# EasyEda_SCH_tally_light_-_main_board_202.net
KiCad netlist of a schematic drawn in EasyEDA
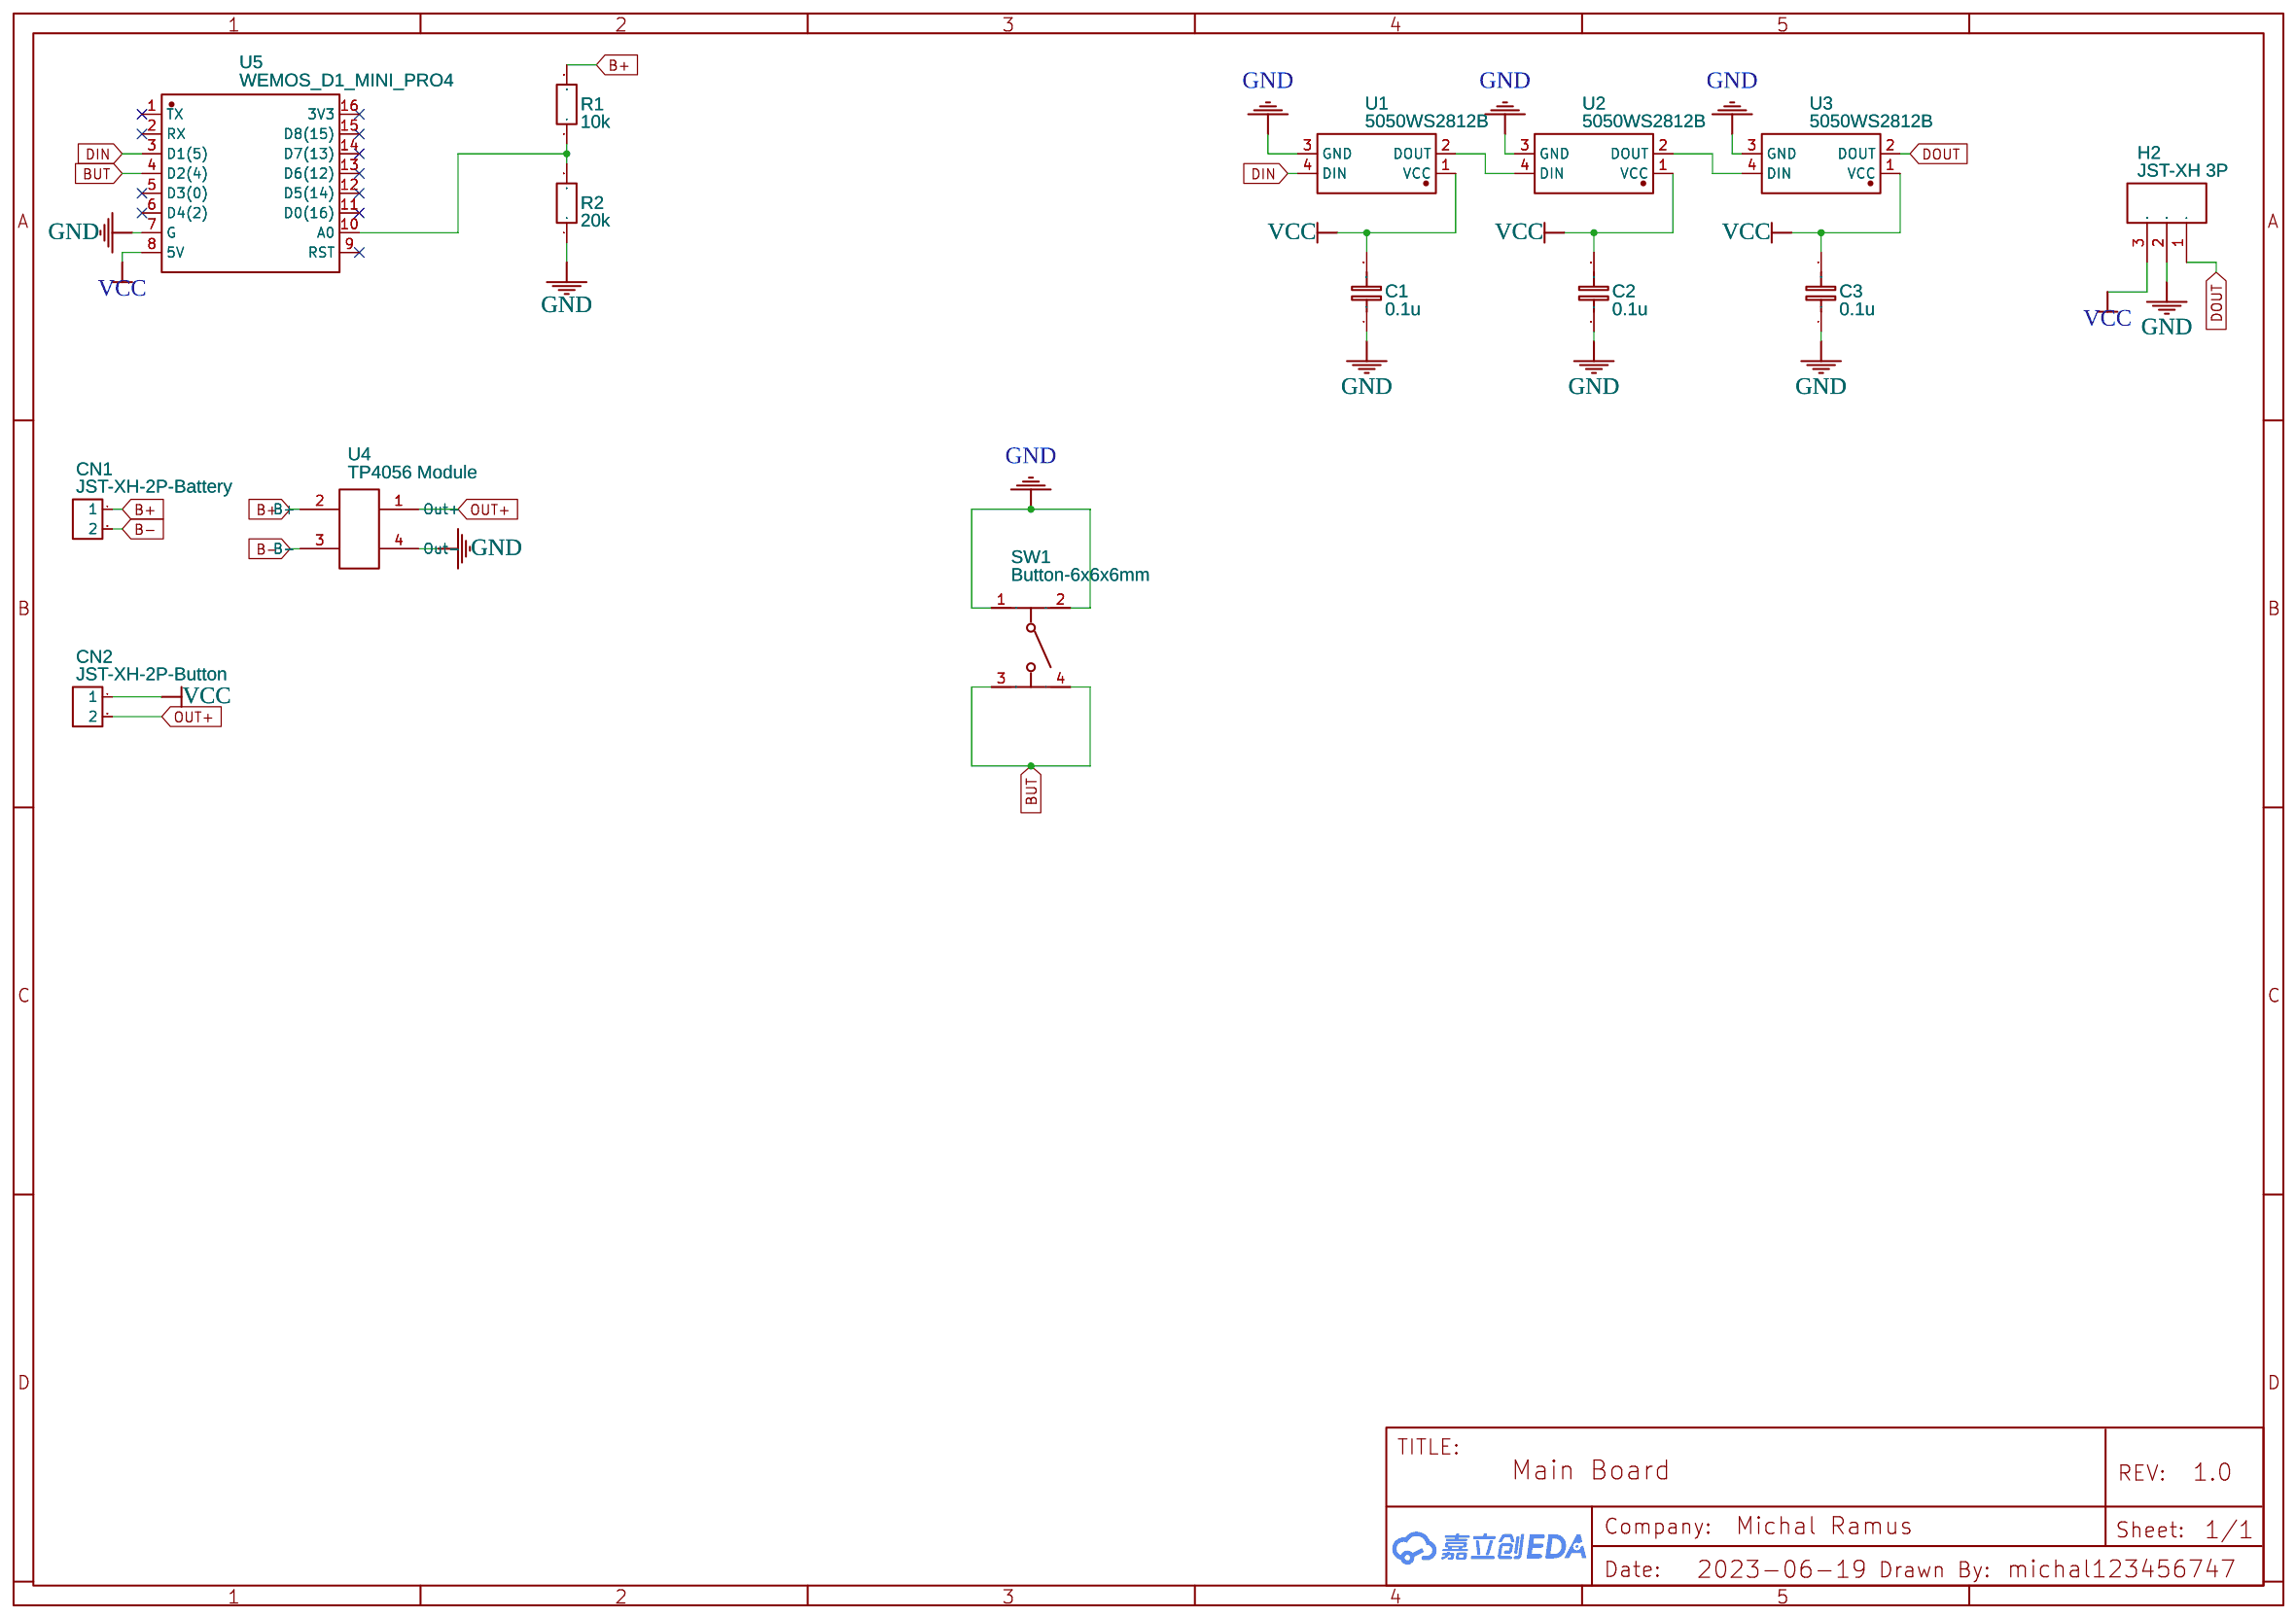
[diagram p0: schematic sheet]

(export (version "E")
  (design (tool "Eeschema 10.0.6"))
  (components
    (comp (ref "C1") (value "0.1u") (libsource (lib "") (part "C_0603_EU")))
    (comp (ref "C2") (value "0.1u") (libsource (lib "") (part "C_0603_EU")))
    (comp (ref "C3") (value "0.1u") (libsource (lib "") (part "C_0603_EU")))
    (comp (ref "CN1")
      (value "JST-XH-2P-Battery")
      (fields (field (name "Manufacturer Part") "JST-XH-2P-M") (field (name "Manufacturer") "JST"))
      (libsource (lib "") (part "JST-XH-2P"))
    )
    (comp (ref "CN2")
      (value "JST-XH-2P-Button")
      (fields (field (name "Manufacturer Part") "JST-XH-2P-M") (field (name "Manufacturer") "JST"))
      (libsource (lib "") (part "JST-XH-2P"))
    )
    (comp (ref "H2") (value "JST-XH 3P") (libsource (lib "") (part "JST-XH 3P")))
    (comp (ref "R1") (value "10k") (libsource (lib "") (part "R_0603_EU")))
    (comp (ref "R2") (value "20k") (libsource (lib "") (part "R_0603_EU")))
    (comp (ref "SW1")
      (value "Button-6x6x6mm")
      (fields
        (field (name "Manufacturer Part") "Switch,6*6*6Plastic head,260G, 0.25mm,Straight line")
        (field (name "Manufacturer") "BBJ")
      )
      (libsource (lib "") (part "Button-6x6x6mm"))
    )
    (comp (ref "U1") (value "5050WS2812B") (libsource (lib "") (part "5050WS2812B")))
    (comp (ref "U2") (value "5050WS2812B") (libsource (lib "") (part "5050WS2812B")))
    (comp (ref "U3") (value "5050WS2812B") (libsource (lib "") (part "5050WS2812B")))
    (comp (ref "U4") (value "TP4056 Module") (libsource (lib "") (part "TP4056 Module")))
    (comp (ref "U5")
      (value "WEMOS_D1_MINI_PRO4")
      (fields (field (name "Manufacturer Part") "Wemos_D1_mini_Pro4"))
      (libsource (lib "") (part "WEMOS_D1_MINI_PRO4"))
    )
  )
  (nets
    (net (code "1") (name "B+") (class "Default")
      (node (ref "CN1") (pin "1") (pinfunction "1_1") (pintype "unspecified"))
      (node (ref "R1") (pin "2") (pinfunction "2_2") (pintype "unspecified"))
      (node (ref "U4") (pin "2") (pinfunction "B+_2") (pintype "unspecified"))
    )
    (net (code "2") (name "B-") (class "Default")
      (node (ref "CN1") (pin "2") (pinfunction "2_2") (pintype "unspecified"))
      (node (ref "U4") (pin "3") (pinfunction "B-_3") (pintype "unspecified"))
    )
    (net (code "3") (name "BUT") (class "Default")
      (node (ref "SW1") (pin "3") (pinfunction "3_3") (pintype "unspecified"))
      (node (ref "SW1") (pin "4") (pinfunction "4_4") (pintype "unspecified"))
      (node (ref "U5") (pin "4") (pinfunction "D2(4)_4") (pintype "unspecified"))
    )
    (net (code "4") (name "DIN") (class "Default")
      (node (ref "U1") (pin "4") (pinfunction "DIN_4") (pintype "unspecified"))
      (node (ref "U5") (pin "3") (pinfunction "D1(5)_3") (pintype "unspecified"))
    )
    (net (code "5") (name "DOUT") (class "Default")
      (node (ref "H2") (pin "1") (pinfunction "1_1") (pintype "unspecified"))
      (node (ref "U3") (pin "2") (pinfunction "DOUT_2") (pintype "unspecified"))
    )
    (net (code "6") (name "GND") (class "Default")
      (node (ref "C1") (pin "1") (pinfunction "1_1") (pintype "unspecified"))
      (node (ref "C2") (pin "1") (pinfunction "1_1") (pintype "unspecified"))
      (node (ref "C3") (pin "1") (pinfunction "1_1") (pintype "unspecified"))
      (node (ref "H2") (pin "2") (pinfunction "2_2") (pintype "unspecified"))
      (node (ref "R2") (pin "1") (pinfunction "1_1") (pintype "unspecified"))
      (node (ref "SW1") (pin "1") (pinfunction "1_1") (pintype "unspecified"))
      (node (ref "SW1") (pin "2") (pinfunction "2_2") (pintype "unspecified"))
      (node (ref "U1") (pin "3") (pinfunction "GND_3") (pintype "unspecified"))
      (node (ref "U2") (pin "3") (pinfunction "GND_3") (pintype "unspecified"))
      (node (ref "U3") (pin "3") (pinfunction "GND_3") (pintype "unspecified"))
      (node (ref "U4") (pin "4") (pinfunction "Out-_4") (pintype "unspecified"))
      (node (ref "U5") (pin "7") (pinfunction "G_7") (pintype "unspecified"))
    )
    (net (code "7") (name "Net-(U1-DOUT)") (class "Default")
      (node (ref "U1") (pin "2") (pinfunction "DOUT_2") (pintype "unspecified"))
      (node (ref "U2") (pin "4") (pinfunction "DIN_4") (pintype "unspecified"))
    )
    (net (code "8") (name "Net-(U2-DOUT)") (class "Default")
      (node (ref "U2") (pin "2") (pinfunction "DOUT_2") (pintype "unspecified"))
      (node (ref "U3") (pin "4") (pinfunction "DIN_4") (pintype "unspecified"))
    )
    (net (code "9") (name "Net-(U5-A0)") (class "Default")
      (node (ref "R1") (pin "1") (pinfunction "1_1") (pintype "unspecified"))
      (node (ref "R2") (pin "2") (pinfunction "2_2") (pintype "unspecified"))
      (node (ref "U5") (pin "10") (pinfunction "A0_10") (pintype "unspecified"))
    )
    (net (code "10") (name "OUT+") (class "Default")
      (node (ref "CN2") (pin "2") (pinfunction "2_2") (pintype "unspecified"))
      (node (ref "U4") (pin "1") (pinfunction "Out+_1") (pintype "unspecified"))
    )
    (net (code "11") (name "VCC") (class "Default")
      (node (ref "C1") (pin "2") (pinfunction "2_2") (pintype "unspecified"))
      (node (ref "C2") (pin "2") (pinfunction "2_2") (pintype "unspecified"))
      (node (ref "C3") (pin "2") (pinfunction "2_2") (pintype "unspecified"))
      (node (ref "CN2") (pin "1") (pinfunction "1_1") (pintype "unspecified"))
      (node (ref "H2") (pin "3") (pinfunction "3_3") (pintype "unspecified"))
      (node (ref "U1") (pin "1") (pinfunction "VCC_1") (pintype "unspecified"))
      (node (ref "U2") (pin "1") (pinfunction "VCC_1") (pintype "unspecified"))
      (node (ref "U3") (pin "1") (pinfunction "VCC_1") (pintype "unspecified"))
      (node (ref "U5") (pin "8") (pinfunction "5V_8") (pintype "unspecified"))
    )
    (net (code "12") (name "unconnected-(U5-3V3-Pad16)") (class "Default")
      (node (ref "U5") (pin "16") (pinfunction "3V3_16") (pintype "unspecified+no_connect"))
    )
    (net (code "13") (name "unconnected-(U5-D0(16)-Pad11)") (class "Default")
      (node (ref "U5") (pin "11") (pinfunction "D0(16)_11") (pintype "unspecified+no_connect"))
    )
    (net (code "14") (name "unconnected-(U5-D3(0)-Pad5)") (class "Default")
      (node (ref "U5") (pin "5") (pinfunction "D3(0)_5") (pintype "unspecified+no_connect"))
    )
    (net (code "15") (name "unconnected-(U5-D4(2)-Pad6)") (class "Default")
      (node (ref "U5") (pin "6") (pinfunction "D4(2)_6") (pintype "unspecified+no_connect"))
    )
    (net (code "16") (name "unconnected-(U5-D5(14)-Pad12)") (class "Default")
      (node (ref "U5") (pin "12") (pinfunction "D5(14)_12") (pintype "unspecified+no_connect"))
    )
    (net (code "17") (name "unconnected-(U5-D6(12)-Pad13)") (class "Default")
      (node (ref "U5") (pin "13") (pinfunction "D6(12)_13") (pintype "unspecified+no_connect"))
    )
    (net (code "18") (name "unconnected-(U5-D7(13)-Pad14)") (class "Default")
      (node (ref "U5") (pin "14") (pinfunction "D7(13)_14") (pintype "unspecified+no_connect"))
    )
    (net (code "19") (name "unconnected-(U5-D8(15)-Pad15)") (class "Default")
      (node (ref "U5") (pin "15") (pinfunction "D8(15)_15") (pintype "unspecified+no_connect"))
    )
    (net (code "20") (name "unconnected-(U5-RST-Pad9)") (class "Default")
      (node (ref "U5") (pin "9") (pinfunction "RST_9") (pintype "unspecified+no_connect"))
    )
    (net (code "21") (name "unconnected-(U5-RX-Pad2)") (class "Default")
      (node (ref "U5") (pin "2") (pinfunction "RX_2") (pintype "unspecified+no_connect"))
    )
    (net (code "22") (name "unconnected-(U5-TX-Pad1)") (class "Default")
      (node (ref "U5") (pin "1") (pinfunction "TX_1") (pintype "unspecified+no_connect"))
    )
  )
)
